# Thunder-Refix.net
KiCad netlist of a schematic drawn in Altium Designer
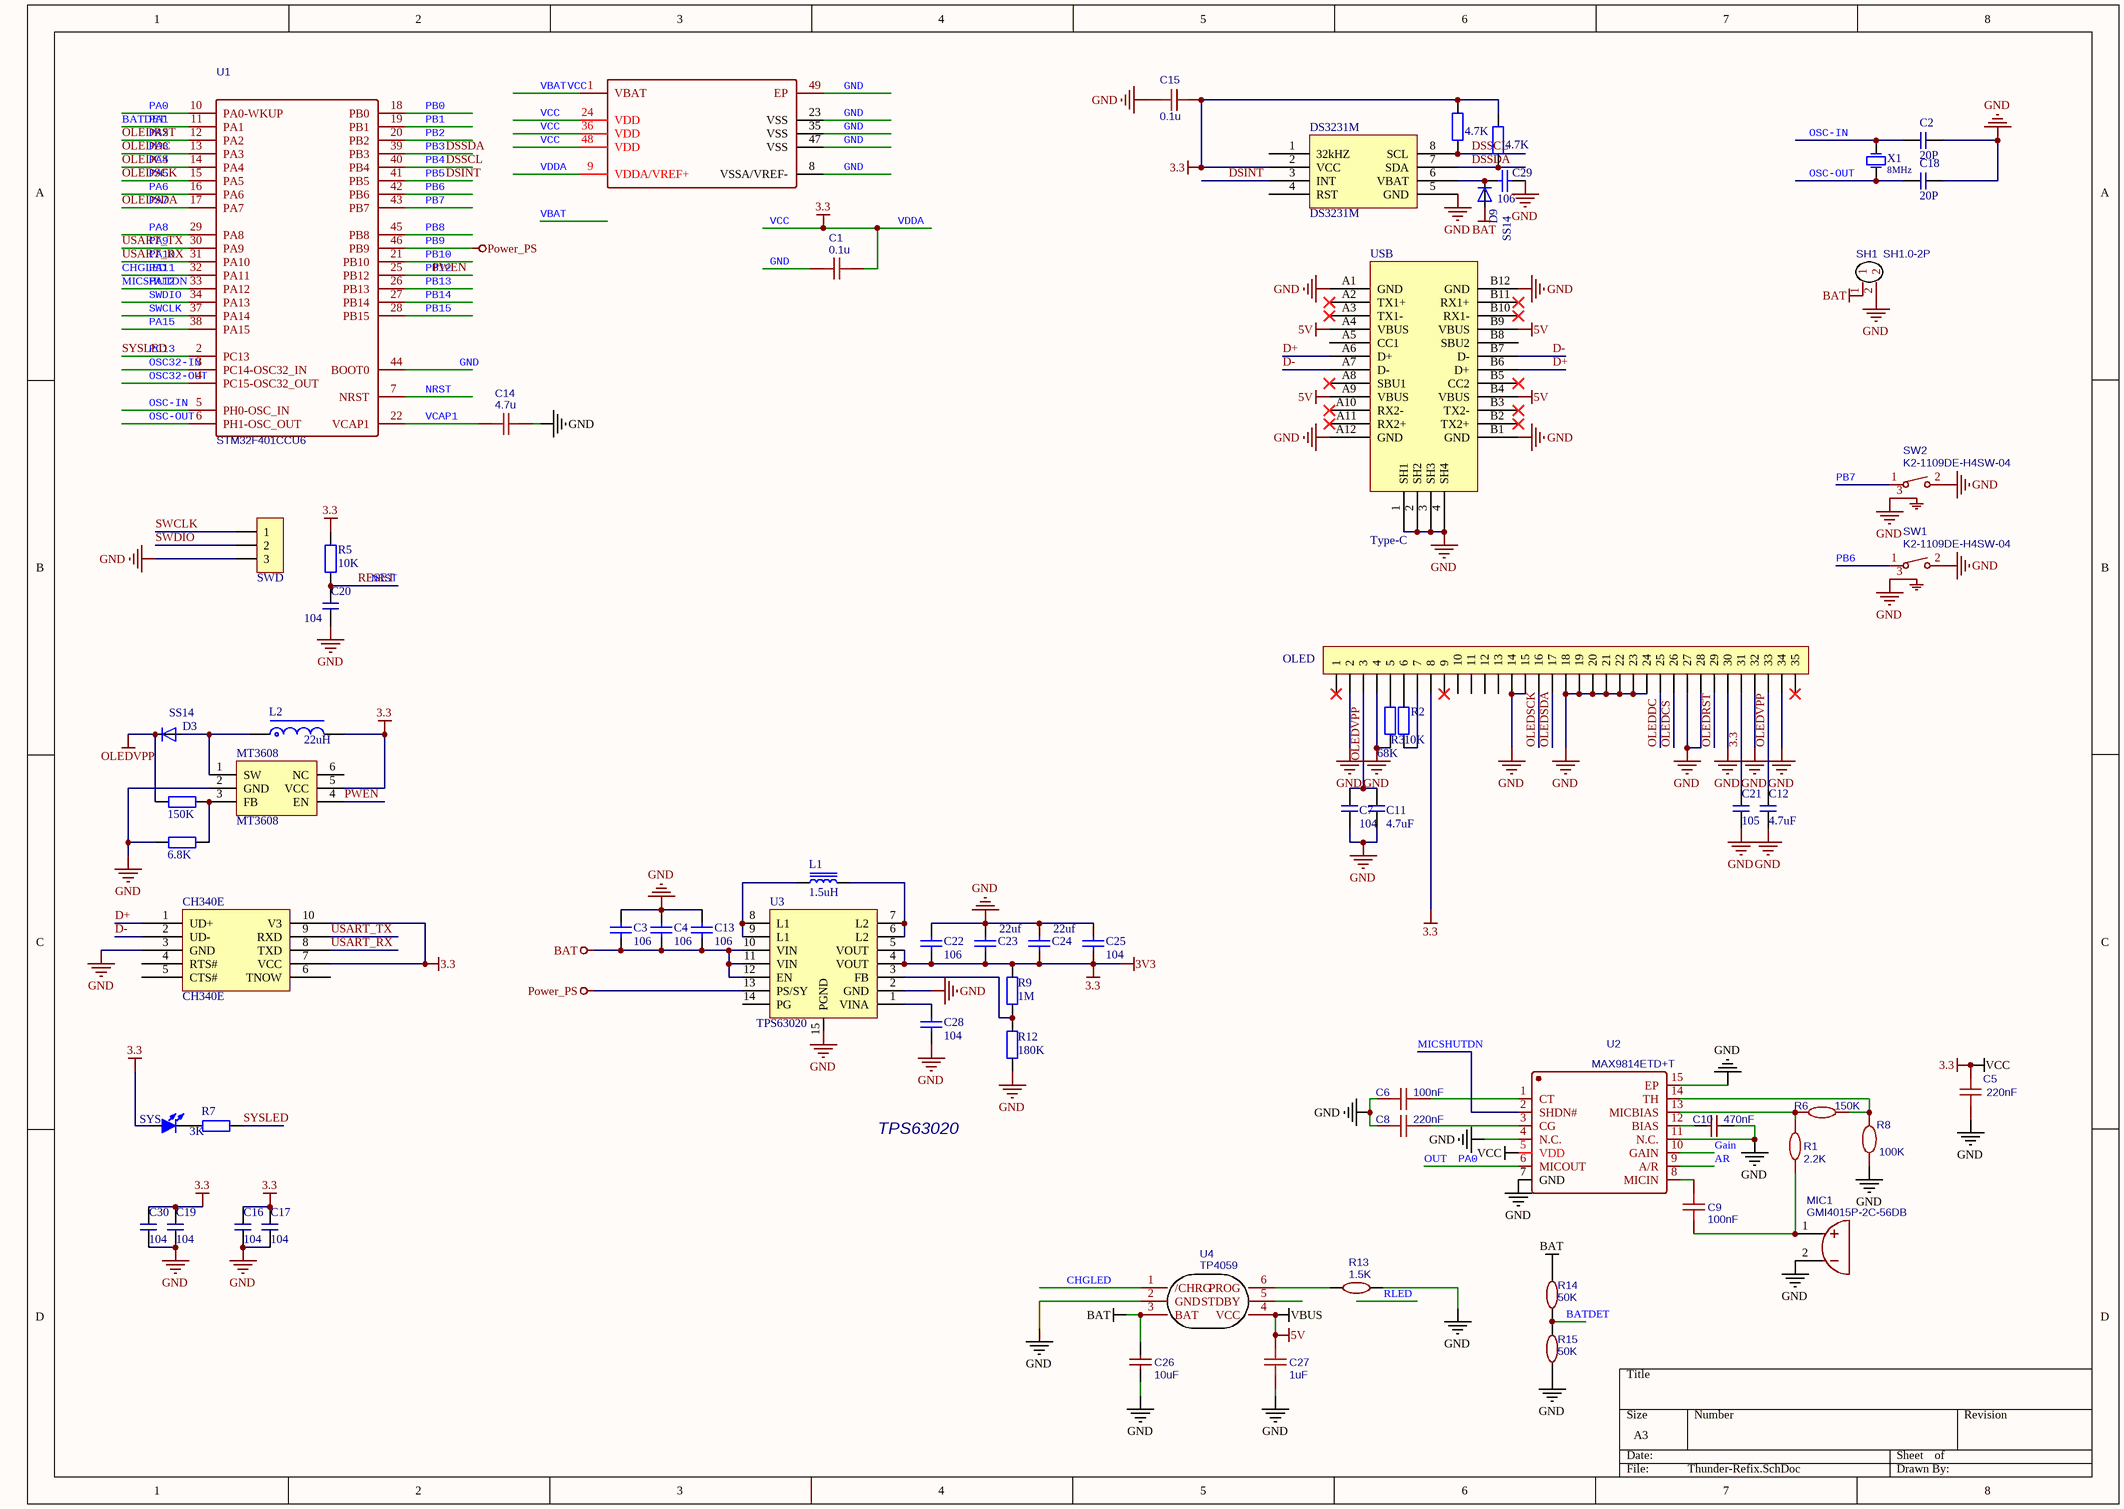
[diagram p0: Thunder-Refix.SchDoc]

(export (version "E")
  (design (tool "Eeschema 10.0.6"))
  (components
    (comp (ref "C1")
      (value "0.1u")
      (footprint "0603C")
      (fields (field (name "CONTRIBUTOR") "LCEDA_Lib"))
      (libsource (lib "altium-import") (part "root_2_0.1u_"))
    )
    (comp (ref "C2") (value "20P") (footprint "0603C") (libsource (lib "Schlib1") (part "电容")))
    (comp (ref "C3")
      (value "106")
      (footprint "我的PCB库:0603c")
      (fields (field (name "C") "106"))
      (libsource (lib "元件库") (part "cap"))
    )
    (comp (ref "C4")
      (value "106")
      (footprint "我的PCB库:0603c")
      (fields (field (name "C") "106"))
      (libsource (lib "元件库") (part "cap"))
    )
    (comp (ref "C5")
      (value "220nF")
      (footprint "0603c")
      (fields
        (field (name "BOM_SUPPLIER PART") "C354366")
        (field (name "BOM_MANUFACTURER PART") "GCJ21BR71H224KA01L")
        (field (name "CONTRIBUTOR") "LCSC")
      )
      (libsource (lib "altium-import") (part "root_1_220nF_"))
    )
    (comp (ref "C6")
      (value "100nF")
      (footprint "0603c")
      (fields
        (field (name "BOM_SUPPLIER PART") "C444732")
        (field (name "BOM_MANUFACTURER PART") "FS055C104K4Z2A")
        (field (name "CONTRIBUTOR") "LCSC")
      )
      (libsource (lib "altium-import") (part "root_1_100nF_"))
    )
    (comp (ref "C7") (value "104") (footprint "0603C") (libsource (lib "Schlib1") (part "电容")))
    (comp (ref "C8")
      (value "220nF")
      (footprint "0603c")
      (fields
        (field (name "BOM_SUPPLIER PART") "C354366")
        (field (name "BOM_MANUFACTURER PART") "GCJ21BR71H224KA01L")
        (field (name "CONTRIBUTOR") "LCSC")
      )
      (libsource (lib "altium-import") (part "root_0_220nF_"))
    )
    (comp (ref "C9")
      (value "100nF")
      (footprint "0603c")
      (fields
        (field (name "BOM_SUPPLIER PART") "C444732")
        (field (name "BOM_MANUFACTURER PART") "FS055C104K4Z2A")
        (field (name "CONTRIBUTOR") "LCSC")
      )
      (libsource (lib "altium-import") (part "root_0_100nF_"))
    )
    (comp (ref "C10")
      (value "470nF")
      (footprint "0603c")
      (fields
        (field (name "BOM_MANUFACTURER PART") "CL21B474KBFNNNE")
        (field (name "BOM_SUPPLIER PART") "C13967")
      )
      (libsource (lib "altium-import") (part "root_0_470nF_"))
    )
    (comp (ref "C11") (value "4.7uF") (footprint "0603C") (libsource (lib "Schlib1") (part "电容")))
    (comp (ref "C12") (value "4.7uF") (footprint "0603C") (libsource (lib "Schlib1") (part "电容")))
    (comp (ref "C13")
      (value "106")
      (footprint "0603c")
      (fields (field (name "C") "106"))
      (libsource (lib "元件库") (part "cap"))
    )
    (comp (ref "C14")
      (value "4.7u")
      (footprint "0603C")
      (fields (field (name "CONTRIBUTOR") "LCEDA_Lib"))
      (libsource (lib "altium-import") (part "root_0_4.7u_"))
    )
    (comp (ref "C15")
      (value "0.1u")
      (footprint "0603C")
      (fields (field (name "CONTRIBUTOR") "LCEDA_Lib"))
      (libsource (lib "altium-import") (part "root_2_0.1u_"))
    )
    (comp (ref "C16") (value "104") (footprint "0603C") (libsource (lib "Schlib1") (part "电容")))
    (comp (ref "C17") (value "104") (footprint "0603C") (libsource (lib "Schlib1") (part "电容")))
    (comp (ref "C18") (value "20P") (footprint "0603C") (libsource (lib "Schlib1") (part "电容")))
    (comp (ref "C19") (value "104") (footprint "0603C") (libsource (lib "Schlib1") (part "电容")))
    (comp (ref "C20") (value "104") (footprint "0603C") (libsource (lib "Schlib1") (part "电容")))
    (comp (ref "C21") (value "105") (footprint "0603C") (libsource (lib "Schlib1") (part "电容")))
    (comp (ref "C22")
      (value "106")
      (footprint "0603c")
      (fields (field (name "C") "106"))
      (libsource (lib "元件库") (part "cap"))
    )
    (comp (ref "C23")
      (value "22uf")
      (footprint "0603c")
      (fields (field (name "C") "22uf"))
      (libsource (lib "元件库") (part "cap"))
    )
    (comp (ref "C24")
      (value "22uf")
      (footprint "0603c")
      (fields (field (name "C") "22uf"))
      (libsource (lib "元件库") (part "cap"))
    )
    (comp (ref "C25")
      (value "104")
      (footprint "0603c")
      (fields (field (name "C") "104"))
      (libsource (lib "元件库") (part "cap"))
    )
    (comp (ref "C26")
      (value "10uF")
      (footprint "0603c")
      (fields
        (field (name "BOM_SUPPLIER PART") "C162317")
        (field (name "BOM_MANUFACTURER PART") "GRM21BB31C106KE15L")
        (field (name "CONTRIBUTOR") "LCSC")
      )
      (libsource (lib "altium-import") (part "root_1_10uF_"))
    )
    (comp (ref "C27")
      (value "1uF")
      (footprint "0603c")
      (fields
        (field (name "BOM_SUPPLIER PART") "C319195")
        (field (name "BOM_MANUFACTURER PART") "UMK212BJ105KG-T")
        (field (name "CONTRIBUTOR") "LCSC")
      )
      (libsource (lib "altium-import") (part "root_1_1uF_"))
    )
    (comp (ref "C28")
      (value "104")
      (footprint "0603c")
      (fields (field (name "C") "104"))
      (libsource (lib "元件库") (part "cap"))
    )
    (comp (ref "C29")
      (value "106")
      (footprint "0603c")
      (fields (field (name "C") "106"))
      (libsource (lib "元件库") (part "cap"))
    )
    (comp (ref "C30") (value "104") (footprint "0603C") (libsource (lib "Schlib1") (part "电容")))
    (comp (ref "CH340E") (value "CH340E") (footprint "MSOP10_L") (libsource (lib "CUBE_T1") (part "CH340E")))
    (comp (ref "D3")
      (value "SS14")
      (footprint "SOD323_1N4148WS")
      (description "Diode Switching 75V 0.3A 2-Pin SOD-323 T/R")
      (fields (field (name "MF") "ON Semiconductor") (field (name "MP") "1N4148WS"))
      (libsource (lib "1N4148WS") (part "1N4148WS"))
    )
    (comp (ref "D9")
      (value "SS14")
      (footprint "SOD323_1N4148WS")
      (description "Diode Switching 75V 0.3A 2-Pin SOD-323 T/R")
      (fields (field (name "MF") "ON Semiconductor") (field (name "MP") "1N4148WS"))
      (libsource (lib "1N4148WS") (part "1N4148WS"))
    )
    (comp (ref "DS3231M") (value "DS3231M") (footprint "SOP8") (libsource (lib "CUBE_T1") (part "DS3231M")))
    (comp (ref "L1")
      (value "1.5uH")
      (footprint "我的PCB库:IND-SMD_L3.0-W3.0_NR3010")
      (fields (field (name "_VALUE") "1.5uH"))
      (libsource (lib "元件库") (part "Inductor Iron 2"))
    )
    (comp (ref "L2")
      (value "22uH")
      (footprint "IND-SMD_L3.0-W3.0_NR3010")
      (description "功率屏蔽电感")
      (fields (field (name "版权归属") "源创客"))
      (libsource (lib "3.1   - 电阻-电容-电感") (part "L-CDRH"))
    )
    (comp (ref "MIC1")
      (value "GMI4015P-2C-56DB")
      (footprint "MIC-TH_BD4.0-P2.00-D0.4-L-FD")
      (fields
        (field (name "BOM_SUPPLIER PART") "C233299")
        (field (name "BOM_MANUFACTURER PART") "GMI4015P-2C-56db")
        (field (name "CONTRIBUTOR") "LCSC")
      )
      (libsource (lib "altium-import") (part "root_0_GMI4015P-2C-56DB_"))
    )
    (comp (ref "MT3608")
      (value "MT3608")
      (footprint "SOT23-6N")
      (description "可调升压芯片")
      (fields (field (name "版权归属") "源创客"))
      (libsource (lib "1.3   - 电源类芯片") (part "SX1308"))
    )
    (comp (ref "OLED")
      (value "FPC1.0-35P")
      (footprint "1.69 OLED")
      (description "FPC连接器")
      (fields (field (name "版权归属") "源创客"))
      (libsource (lib "4.14 - FPC连接器") (part "FPC-35P"))
    )
    (comp (ref "R1")
      (value "2.2K")
      (footprint "0603r")
      (fields
        (field (name "BOM_SUPPLIER PART") "C325769")
        (field (name "BOM_MANUFACTURER PART") "RMC08052.2K1%N")
        (field (name "CONTRIBUTOR") "LCSC")
      )
      (libsource (lib "altium-import") (part "root_1_2.2K_"))
    )
    (comp (ref "R2")
      (value "10K")
      (footprint "0603R")
      (description "贴片电阻")
      (fields (field (name "版权归属") "源创客"))
      (libsource (lib "3.1   - 电阻-电容-电感") (part "R"))
    )
    (comp (ref "R3")
      (value "68K")
      (footprint "0603R")
      (description "贴片电阻")
      (fields (field (name "版权归属") "源创客"))
      (libsource (lib "3.1   - 电阻-电容-电感") (part "R"))
    )
    (comp (ref "R5")
      (value "10K")
      (footprint "0603R")
      (description "贴片电阻")
      (fields (field (name "版权归属") "源创客"))
      (libsource (lib "3.1   - 电阻-电容-电感") (part "R"))
    )
    (comp (ref "R6")
      (value "150K")
      (footprint "0603r")
      (fields
        (field (name "BOM_SUPPLIER PART") "C325765")
        (field (name "BOM_MANUFACTURER PART") "RMC0805150K1%N")
        (field (name "CONTRIBUTOR") "LCSC")
      )
      (libsource (lib "altium-import") (part "root_0_150K_"))
    )
    (comp (ref "R7")
      (value "3K")
      (footprint "0603R")
      (description "贴片电阻")
      (fields (field (name "版权归属") "源创客"))
      (libsource (lib "3.1   - 电阻-电容-电感") (part "R"))
    )
    (comp (ref "R8")
      (value "100K")
      (footprint "0603r")
      (fields
        (field (name "BOM_SUPPLIER PART") "C346756")
        (field (name "BOM_MANUFACTURER PART") "RTAN0805BKE100K")
        (field (name "CONTRIBUTOR") "LCSC")
      )
      (libsource (lib "altium-import") (part "root_1_100K_"))
    )
    (comp (ref "R9")
      (value "1M")
      (footprint "0603r")
      (fields (field (name "R") "1M"))
      (libsource (lib "元件库") (part "Res"))
    )
    (comp (ref "R10")
      (value "4.7K")
      (footprint "0603R")
      (description "贴片电阻")
      (fields (field (name "版权归属") "源创客"))
      (libsource (lib "3.1   - 电阻-电容-电感") (part "R"))
    )
    (comp (ref "R11")
      (value "4.7K")
      (footprint "0603R")
      (description "贴片电阻")
      (fields (field (name "版权归属") "源创客"))
      (libsource (lib "3.1   - 电阻-电容-电感") (part "R"))
    )
    (comp (ref "R12")
      (value "180K")
      (footprint "0603r")
      (fields (field (name "R") "180K"))
      (libsource (lib "元件库") (part "Res"))
    )
    (comp (ref "R13")
      (value "1.5K")
      (footprint "0603r")
      (fields
        (field (name "BOM_MANUFACTURER PART") "RC0603FR-071K5L")
        (field (name "BOM_SUPPLIER PART") "C114668")
      )
      (libsource (lib "altium-import") (part "root_0_1.5K_"))
    )
    (comp (ref "R14")
      (value "50K")
      (footprint "0603r")
      (fields
        (field (name "BOM_MANUFACTURER PART") "RC0603FR-071K5L")
        (field (name "BOM_SUPPLIER PART") "C114668")
      )
      (libsource (lib "altium-import") (part "root_1_1.5K_"))
    )
    (comp (ref "R15")
      (value "50K")
      (footprint "0603r")
      (fields
        (field (name "BOM_MANUFACTURER PART") "RC0603FR-071K5L")
        (field (name "BOM_SUPPLIER PART") "C114668")
      )
      (libsource (lib "altium-import") (part "root_1_1.5K_"))
    )
    (comp (ref "RB")
      (value "150K")
      (footprint "0603R")
      (description "贴片电阻")
      (fields (field (name "版权归属") "源创客"))
      (libsource (lib "3.1   - 电阻-电容-电感") (part "R"))
    )
    (comp (ref "RS")
      (value "6.8K")
      (footprint "0603R")
      (description "贴片电阻")
      (fields (field (name "版权归属") "源创客"))
      (libsource (lib "3.1   - 电阻-电容-电感") (part "R"))
    )
    (comp (ref "SH1")
      (value "SH1.0-2P")
      (footprint "SH1.0-2P")
      (fields (field (name "CONTRIBUTOR") "perry2867"))
      (libsource (lib "altium-import") (part "root_1_SH1.0-2P_"))
    )
    (comp (ref "SW1")
      (value "K2-1109DE-H4SW-04")
      (footprint "KEY-TH_K2-1109DE-CXXW-XX")
      (fields (field (name "BOM_SUPPLIER PART") "C961730") (field (name "CONTRIBUTOR") "LCSC"))
      (libsource (lib "altium-import") (part "root_0_K2-1109DE-H4SW-04_"))
    )
    (comp (ref "SW2")
      (value "K2-1109DE-H4SW-04")
      (footprint "KEY-TH_K2-1109DE-CXXW-XX")
      (fields (field (name "BOM_SUPPLIER PART") "C961730") (field (name "CONTRIBUTOR") "LCSC"))
      (libsource (lib "altium-import") (part "root_0_K2-1109DE-H4SW-04_"))
    )
    (comp (ref "SWD")
      (value "HDR-1X3")
      (footprint "ZH1.5-LI-3P")
      (description "3P接插件")
      (fields (field (name "版权归属") "源创客"))
      (libsource (lib "4.3   - 接插件-脚距1.5") (part "Header 3"))
    )
    (comp (ref "SYS")
      (value "粉色")
      (footprint "0603LED")
      (description "方形LED")
      (fields (field (name "版权归属") "源创客"))
      (libsource (lib "9.1   - LED") (part "LED-F234"))
    )
    (comp (ref "U1")
      (value "STM32F401CCU6")
      (footprint "QFN48 7X7_N")
      (fields (field (name "BOM_SUPPLIER PART") "C79861") (field (name "SUBPART_NO") "1"))
      (libsource (lib "Galaxy") (part "STM32F401CCU6"))
    )
    (comp (ref "U2")
      (value "MAX9814ETD+T")
      (footprint "TDFN-14_L3.0-W3.0-P0.40-BL-EP")
      (fields (field (name "BOM_SUPPLIER PART") "C41714"))
      (libsource (lib "altium-import") (part "root_0_MAX9814ETD+T_"))
    )
    (comp (ref "U3")
      (value "TPS63020")
      (footprint "我的PCB库:TPS63020")
      (libsource (lib "我的元件库") (part "TPS63020"))
    )
    (comp (ref "U4")
      (value "TP4059")
      (footprint "SOT23-6N")
      (fields (field (name "BOM_SUPPLIER PART") "C80364"))
      (libsource (lib "altium-import") (part "root_0_TP4059_"))
    )
    (comp (ref "USB") (value "Type-C") (footprint "Type-C") (libsource (lib "元件") (part "Type-C")))
    (comp (ref "X1")
      (value "8MHz")
      (footprint "OSC 5032-2P")
      (description "XTAL,8MHz,±20PPM,12.6*4.5")
      (fields (field (name "Comment") "1.6.1.01.005.001"))
      (libsource (lib "Mark_7") (part "1.6.1.01.005.001"))
    )
  )
  (nets
    (net (code "1") (name "/AR") (class "Default")
      (node (ref "U2") (pin "9") (pinfunction "A/R_9") (pintype "passive"))
    )
    (net (code "2") (name "/BATDET") (class "Default")
      (node (ref "R14") (pin "1") (pinfunction "1_1") (pintype "passive"))
      (node (ref "R15") (pin "2") (pinfunction "2_2") (pintype "passive"))
      (node (ref "U1") (pin "11") (pinfunction "PA1_11") (pintype "passive"))
    )
    (net (code "3") (name "/CHGLED") (class "Default")
      (node (ref "U1") (pin "32") (pinfunction "PA11_32") (pintype "passive"))
      (node (ref "U4") (pin "1") (pinfunction "/CHRG_1") (pintype "passive"))
    )
    (net (code "4") (name "/D+") (class "Default")
      (node (ref "CH340E") (pin "1") (pinfunction "UD+_1") (pintype "passive"))
      (node (ref "USB") (pin "A6") (pinfunction "D+_A6") (pintype "passive"))
      (node (ref "USB") (pin "B6") (pinfunction "D+_B6") (pintype "passive"))
    )
    (net (code "5") (name "/D-") (class "Default")
      (node (ref "CH340E") (pin "2") (pinfunction "UD-_2") (pintype "passive"))
      (node (ref "USB") (pin "A7") (pinfunction "D-_A7") (pintype "passive"))
      (node (ref "USB") (pin "B7") (pinfunction "D-_B7") (pintype "passive"))
    )
    (net (code "6") (name "/DSINT") (class "Default")
      (node (ref "DS3231M") (pin "3") (pinfunction "INT_3") (pintype "passive"))
      (node (ref "U1") (pin "41") (pinfunction "PB5_41") (pintype "passive"))
    )
    (net (code "7") (name "/DSSCL") (class "Default")
      (node (ref "DS3231M") (pin "8") (pinfunction "SCL_8") (pintype "passive"))
      (node (ref "R10") (pin "2") (pinfunction "2_2") (pintype "passive"))
      (node (ref "U1") (pin "40") (pinfunction "PB4_40") (pintype "passive"))
    )
    (net (code "8") (name "/DSSDA") (class "Default")
      (node (ref "DS3231M") (pin "7") (pinfunction "SDA_7") (pintype "passive"))
      (node (ref "R11") (pin "2") (pinfunction "2_2") (pintype "passive"))
      (node (ref "U1") (pin "39") (pinfunction "PB3_39") (pintype "passive"))
    )
    (net (code "9") (name "/Gain") (class "Default")
      (node (ref "U2") (pin "10") (pinfunction "GAIN_10") (pintype "passive"))
    )
    (net (code "10") (name "/MICSHUTDN") (class "Default")
      (node (ref "U1") (pin "33") (pinfunction "PA12_33") (pintype "passive"))
      (node (ref "U2") (pin "2") (pinfunction "SHDN#_2") (pintype "passive"))
    )
    (net (code "11") (name "/NRST") (class "Default")
      (node (ref "C20") (pin "1") (pinfunction "1_1") (pintype "passive"))
      (node (ref "R5") (pin "2") (pinfunction "2_2") (pintype "passive"))
      (node (ref "U1") (pin "7") (pinfunction "NRST_7") (pintype "passive"))
    )
    (net (code "12") (name "/OLEDCS") (class "Default")
      (node (ref "OLED") (pin "26") (pinfunction "26_26") (pintype "passive"))
      (node (ref "U1") (pin "14") (pinfunction "PA4_14") (pintype "passive"))
    )
    (net (code "13") (name "/OLEDDC") (class "Default")
      (node (ref "OLED") (pin "25") (pinfunction "25_25") (pintype "passive"))
      (node (ref "U1") (pin "13") (pinfunction "PA3_13") (pintype "passive"))
    )
    (net (code "14") (name "/OLEDRST") (class "Default")
      (node (ref "OLED") (pin "29") (pinfunction "29_29") (pintype "passive"))
      (node (ref "U1") (pin "12") (pinfunction "PA2_12") (pintype "passive"))
    )
    (net (code "15") (name "/OLEDSCK") (class "Default")
      (node (ref "OLED") (pin "16") (pinfunction "16_16") (pintype "passive"))
      (node (ref "U1") (pin "15") (pinfunction "PA5_15") (pintype "passive"))
    )
    (net (code "16") (name "/OLEDSDA") (class "Default")
      (node (ref "OLED") (pin "17") (pinfunction "17_17") (pintype "passive"))
      (node (ref "U1") (pin "17") (pinfunction "PA7_17") (pintype "passive"))
    )
    (net (code "17") (name "/OSC-IN") (class "Default")
      (node (ref "C2") (pin "2") (pinfunction "2_2") (pintype "passive"))
      (node (ref "U1") (pin "5") (pinfunction "PH0-OSC_IN_5") (pintype "passive"))
      (node (ref "X1") (pin "1") (pinfunction "OSC1_1") (pintype "passive"))
    )
    (net (code "18") (name "/OSC-OUT") (class "Default")
      (node (ref "C18") (pin "2") (pinfunction "2_2") (pintype "passive"))
      (node (ref "U1") (pin "6") (pinfunction "PH1-OSC_OUT_6") (pintype "passive"))
      (node (ref "X1") (pin "2") (pinfunction "OSC2_2") (pintype "passive"))
    )
    (net (code "19") (name "/OSC32-IN") (class "Default")
      (node (ref "U1") (pin "3") (pinfunction "PC14-OSC32_IN_3") (pintype "passive"))
    )
    (net (code "20") (name "/OSC32-OUT") (class "Default")
      (node (ref "U1") (pin "4") (pinfunction "PC15-OSC32_OUT_4") (pintype "passive"))
    )
    (net (code "21") (name "/OUT") (class "Default")
      (node (ref "U1") (pin "10") (pinfunction "PA0-WKUP_10") (pintype "passive"))
      (node (ref "U2") (pin "6") (pinfunction "MICOUT_6") (pintype "passive"))
    )
    (net (code "22") (name "/PA6") (class "Default")
      (node (ref "U1") (pin "16") (pinfunction "PA6_16") (pintype "passive"))
    )
    (net (code "23") (name "/PA8") (class "Default")
      (node (ref "U1") (pin "29") (pinfunction "PA8_29") (pintype "passive"))
    )
    (net (code "24") (name "/PA9") (class "Default")
      (node (ref "CH340E") (pin "9") (pinfunction "RXD_9") (pintype "passive"))
      (node (ref "U1") (pin "30") (pinfunction "PA9_30") (pintype "passive"))
    )
    (net (code "25") (name "/PA10") (class "Default")
      (node (ref "CH340E") (pin "8") (pinfunction "TXD_8") (pintype "passive"))
      (node (ref "U1") (pin "31") (pinfunction "PA10_31") (pintype "passive"))
    )
    (net (code "26") (name "/PA15") (class "Default")
      (node (ref "U1") (pin "38") (pinfunction "PA15_38") (pintype "passive"))
    )
    (net (code "27") (name "/PB0") (class "Default")
      (node (ref "U1") (pin "18") (pinfunction "PB0_18") (pintype "passive"))
    )
    (net (code "28") (name "/PB1") (class "Default")
      (node (ref "U1") (pin "19") (pinfunction "PB1_19") (pintype "passive"))
    )
    (net (code "29") (name "/PB2") (class "Default")
      (node (ref "U1") (pin "20") (pinfunction "PB2_20") (pintype "passive"))
    )
    (net (code "30") (name "/PB6") (class "Default")
      (node (ref "SW1") (pin "1") (pinfunction "1_1") (pintype "passive"))
      (node (ref "U1") (pin "42") (pinfunction "PB6_42") (pintype "passive"))
    )
    (net (code "31") (name "/PB7") (class "Default")
      (node (ref "SW2") (pin "1") (pinfunction "1_1") (pintype "passive"))
      (node (ref "U1") (pin "43") (pinfunction "PB7_43") (pintype "passive"))
    )
    (net (code "32") (name "/PB8") (class "Default")
      (node (ref "U1") (pin "45") (pinfunction "PB8_45") (pintype "passive"))
    )
    (net (code "33") (name "/PB10") (class "Default")
      (node (ref "U1") (pin "21") (pinfunction "PB10_21") (pintype "passive"))
    )
    (net (code "34") (name "/PB12") (class "Default")
      (node (ref "MT3608") (pin "4") (pinfunction "EN_4") (pintype "passive"))
      (node (ref "U1") (pin "25") (pinfunction "PB12_25") (pintype "passive"))
    )
    (net (code "35") (name "/PB13") (class "Default")
      (node (ref "U1") (pin "26") (pinfunction "PB13_26") (pintype "passive"))
    )
    (net (code "36") (name "/PB14") (class "Default")
      (node (ref "U1") (pin "27") (pinfunction "PB14_27") (pintype "passive"))
    )
    (net (code "37") (name "/PB15") (class "Default")
      (node (ref "U1") (pin "28") (pinfunction "PB15_28") (pintype "passive"))
    )
    (net (code "38") (name "/PC13") (class "Default")
      (node (ref "R7") (pin "1") (pinfunction "1_1") (pintype "passive"))
      (node (ref "U1") (pin "2") (pinfunction "PC13_2") (pintype "passive"))
    )
    (net (code "40") (name "/SWCLK") (class "Default")
      (node (ref "SWD") (pin "1") (pinfunction "1_1") (pintype "passive"))
      (node (ref "U1") (pin "37") (pinfunction "PA14_37") (pintype "passive"))
    )
    (net (code "41") (name "/SWDIO") (class "Default")
      (node (ref "SWD") (pin "2") (pinfunction "2_2") (pintype "passive"))
      (node (ref "U1") (pin "34") (pinfunction "PA13_34") (pintype "passive"))
    )
    (net (code "42") (name "/VCAP1") (class "Default")
      (node (ref "C14") (pin "1") (pinfunction "1_1") (pintype "passive"))
      (node (ref "U1") (pin "22") (pinfunction "VCAP1_22") (pintype "passive"))
    )
    (net (code "43") (name "3.3") (class "Default")
      (node (ref "C1") (pin "1") (pinfunction "1_1") (pintype "passive"))
      (node (ref "C15") (pin "1") (pinfunction "1_1") (pintype "passive"))
      (node (ref "C16") (pin "1") (pinfunction "1_1") (pintype "passive"))
      (node (ref "C17") (pin "1") (pinfunction "1_1") (pintype "passive"))
      (node (ref "C19") (pin "1") (pinfunction "1_1") (pintype "passive"))
      (node (ref "C21") (pin "1") (pinfunction "1_1") (pintype "passive"))
      (node (ref "C22") (pin "1") (pinfunction "1_1") (pintype "passive"))
      (node (ref "C23") (pin "1") (pinfunction "1_1") (pintype "passive"))
      (node (ref "C24") (pin "1") (pinfunction "1_1") (pintype "passive"))
      (node (ref "C25") (pin "1") (pinfunction "1_1") (pintype "passive"))
      (node (ref "C30") (pin "1") (pinfunction "1_1") (pintype "passive"))
      (node (ref "C5") (pin "2") (pinfunction "2_2") (pintype "passive"))
      (node (ref "CH340E") (pin "10") (pinfunction "V3_10") (pintype "passive"))
      (node (ref "CH340E") (pin "7") (pinfunction "VCC_7") (pintype "passive"))
      (node (ref "DS3231M") (pin "2") (pinfunction "VCC_2") (pintype "passive"))
      (node (ref "L2") (pin "2") (pinfunction "2_2") (pintype "passive"))
      (node (ref "MT3608") (pin "5") (pinfunction "VCC_5") (pintype "passive"))
      (node (ref "OLED") (pin "31") (pinfunction "31_31") (pintype "passive"))
      (node (ref "OLED") (pin "8") (pinfunction "8_8") (pintype "passive"))
      (node (ref "R10") (pin "1") (pinfunction "1_1") (pintype "passive"))
      (node (ref "R11") (pin "1") (pinfunction "1_1") (pintype "passive"))
      (node (ref "R5") (pin "1") (pinfunction "1_1") (pintype "passive"))
      (node (ref "R9") (pin "1") (pinfunction "1_1") (pintype "passive"))
      (node (ref "SYS") (pin "1") (pinfunction "A_1") (pintype "passive"))
      (node (ref "U1") (pin "1") (pinfunction "VBAT_1") (pintype "passive"))
      (node (ref "U1") (pin "24") (pinfunction "VDD_24") (pintype "passive"))
      (node (ref "U1") (pin "36") (pinfunction "VDD_36") (pintype "passive"))
      (node (ref "U1") (pin "48") (pinfunction "VDD_48") (pintype "passive"))
      (node (ref "U1") (pin "9") (pinfunction "VDDA/VREF+_9") (pintype "passive"))
      (node (ref "U2") (pin "5") (pinfunction "VDD_5") (pintype "passive"))
      (node (ref "U3") (pin "4") (pinfunction "VOUT_4") (pintype "passive"))
      (node (ref "U3") (pin "5") (pinfunction "VOUT_5") (pintype "passive"))
    )
    (net (code "44") (name "5V") (class "Default")
      (node (ref "C27") (pin "1") (pinfunction "1_1") (pintype "passive"))
      (node (ref "U4") (pin "4") (pinfunction "VCC_4") (pintype "passive"))
      (node (ref "USB") (pin "A4") (pinfunction "VBUS_A4") (pintype "passive"))
      (node (ref "USB") (pin "A9") (pinfunction "VBUS_A9") (pintype "passive"))
      (node (ref "USB") (pin "B4") (pinfunction "VBUS_B4") (pintype "passive"))
      (node (ref "USB") (pin "B9") (pinfunction "VBUS_B9") (pintype "passive"))
    )
    (net (code "45") (name "BAT") (class "Default")
      (node (ref "C13") (pin "1") (pinfunction "1_1") (pintype "passive"))
      (node (ref "C26") (pin "2") (pinfunction "2_2") (pintype "passive"))
      (node (ref "C3") (pin "1") (pinfunction "1_1") (pintype "passive"))
      (node (ref "C4") (pin "1") (pinfunction "1_1") (pintype "passive"))
      (node (ref "D9") (pin "A") (pinfunction "A_A") (pintype "passive"))
      (node (ref "R14") (pin "2") (pinfunction "2_2") (pintype "passive"))
      (node (ref "SH1") (pin "1") (pinfunction "1_1") (pintype "passive"))
      (node (ref "U3") (pin "10") (pinfunction "VIN_10") (pintype "passive"))
      (node (ref "U3") (pin "11") (pinfunction "VIN_11") (pintype "passive"))
      (node (ref "U3") (pin "12") (pinfunction "EN_12") (pintype "passive"))
      (node (ref "U4") (pin "3") (pinfunction "BAT_3") (pintype "passive"))
    )
    (net (code "46") (name "GND") (class "Default")
      (node (ref "C1") (pin "2") (pinfunction "2_2") (pintype "passive"))
      (node (ref "C10") (pin "2") (pinfunction "2_2") (pintype "passive"))
      (node (ref "C11") (pin "2") (pinfunction "2_2") (pintype "passive"))
      (node (ref "C12") (pin "2") (pinfunction "2_2") (pintype "passive"))
      (node (ref "C13") (pin "2") (pinfunction "2_2") (pintype "passive"))
      (node (ref "C14") (pin "2") (pinfunction "2_2") (pintype "passive"))
      (node (ref "C15") (pin "2") (pinfunction "2_2") (pintype "passive"))
      (node (ref "C16") (pin "2") (pinfunction "2_2") (pintype "passive"))
      (node (ref "C17") (pin "2") (pinfunction "2_2") (pintype "passive"))
      (node (ref "C18") (pin "1") (pinfunction "1_1") (pintype "passive"))
      (node (ref "C19") (pin "2") (pinfunction "2_2") (pintype "passive"))
      (node (ref "C2") (pin "1") (pinfunction "1_1") (pintype "passive"))
      (node (ref "C20") (pin "2") (pinfunction "2_2") (pintype "passive"))
      (node (ref "C21") (pin "2") (pinfunction "2_2") (pintype "passive"))
      (node (ref "C22") (pin "2") (pinfunction "2_2") (pintype "passive"))
      (node (ref "C23") (pin "2") (pinfunction "2_2") (pintype "passive"))
      (node (ref "C24") (pin "2") (pinfunction "2_2") (pintype "passive"))
      (node (ref "C25") (pin "2") (pinfunction "2_2") (pintype "passive"))
      (node (ref "C26") (pin "1") (pinfunction "1_1") (pintype "passive"))
      (node (ref "C27") (pin "2") (pinfunction "2_2") (pintype "passive"))
      (node (ref "C28") (pin "1") (pinfunction "1_1") (pintype "passive"))
      (node (ref "C29") (pin "1") (pinfunction "1_1") (pintype "passive"))
      (node (ref "C3") (pin "2") (pinfunction "2_2") (pintype "passive"))
      (node (ref "C30") (pin "2") (pinfunction "2_2") (pintype "passive"))
      (node (ref "C4") (pin "2") (pinfunction "2_2") (pintype "passive"))
      (node (ref "C5") (pin "1") (pinfunction "1_1") (pintype "passive"))
      (node (ref "C6") (pin "1") (pinfunction "1_1") (pintype "passive"))
      (node (ref "C7") (pin "2") (pinfunction "2_2") (pintype "passive"))
      (node (ref "C8") (pin "1") (pinfunction "1_1") (pintype "passive"))
      (node (ref "CH340E") (pin "3") (pinfunction "GND_3") (pintype "passive"))
      (node (ref "DS3231M") (pin "5") (pinfunction "GND_5") (pintype "passive"))
      (node (ref "MIC1") (pin "2") (pinfunction "2_2") (pintype "passive"))
      (node (ref "MT3608") (pin "2") (pinfunction "GND_2") (pintype "passive"))
      (node (ref "OLED") (pin "14") (pinfunction "14_14") (pintype "passive"))
      (node (ref "OLED") (pin "15") (pinfunction "15_15") (pintype "passive"))
      (node (ref "OLED") (pin "18") (pinfunction "18_18") (pintype "passive"))
      (node (ref "OLED") (pin "19") (pinfunction "19_19") (pintype "passive"))
      (node (ref "OLED") (pin "2") (pinfunction "2_2") (pintype "passive"))
      (node (ref "OLED") (pin "20") (pinfunction "20_20") (pintype "passive"))
      (node (ref "OLED") (pin "21") (pinfunction "21_21") (pintype "passive"))
      (node (ref "OLED") (pin "22") (pinfunction "22_22") (pintype "passive"))
      (node (ref "OLED") (pin "23") (pinfunction "23_23") (pintype "passive"))
      (node (ref "OLED") (pin "24") (pinfunction "24_24") (pintype "passive"))
      (node (ref "OLED") (pin "27") (pinfunction "27_27") (pintype "passive"))
      (node (ref "OLED") (pin "28") (pinfunction "28_28") (pintype "passive"))
      (node (ref "OLED") (pin "30") (pinfunction "30_30") (pintype "passive"))
      (node (ref "OLED") (pin "32") (pinfunction "32_32") (pintype "passive"))
      (node (ref "OLED") (pin "34") (pinfunction "34_34") (pintype "passive"))
      (node (ref "OLED") (pin "4") (pinfunction "4_4") (pintype "passive"))
      (node (ref "R12") (pin "2") (pinfunction "2_2") (pintype "passive"))
      (node (ref "R13") (pin "2") (pinfunction "2_2") (pintype "passive"))
      (node (ref "R15") (pin "1") (pinfunction "1_1") (pintype "passive"))
      (node (ref "R3") (pin "1") (pinfunction "1_1") (pintype "passive"))
      (node (ref "R8") (pin "1") (pinfunction "1_1") (pintype "passive"))
      (node (ref "RS") (pin "1") (pinfunction "1_1") (pintype "passive"))
      (node (ref "SH1") (pin "2") (pinfunction "2_2") (pintype "passive"))
      (node (ref "SW1") (pin "2") (pinfunction "2_2") (pintype "passive"))
      (node (ref "SW1") (pin "3") (pinfunction "GND_3") (pintype "passive"))
      (node (ref "SW2") (pin "2") (pinfunction "2_2") (pintype "passive"))
      (node (ref "SW2") (pin "3") (pinfunction "GND_3") (pintype "passive"))
      (node (ref "SWD") (pin "3") (pinfunction "3_3") (pintype "passive"))
      (node (ref "U1") (pin "23") (pinfunction "VSS_23") (pintype "passive"))
      (node (ref "U1") (pin "35") (pinfunction "VSS_35") (pintype "passive"))
      (node (ref "U1") (pin "44") (pinfunction "BOOT0_44") (pintype "passive"))
      (node (ref "U1") (pin "47") (pinfunction "VSS_47") (pintype "passive"))
      (node (ref "U1") (pin "49") (pinfunction "EP_49") (pintype "passive"))
      (node (ref "U1") (pin "8") (pinfunction "VSSA/VREF-_8") (pintype "passive"))
      (node (ref "U2") (pin "11") (pinfunction "N.C._11") (pintype "passive"))
      (node (ref "U2") (pin "15") (pinfunction "EP_15") (pintype "passive"))
      (node (ref "U2") (pin "4") (pinfunction "N.C._4") (pintype "passive"))
      (node (ref "U2") (pin "7") (pinfunction "GND_7") (pintype "passive"))
      (node (ref "U3") (pin "15") (pinfunction "PGND_15") (pintype "passive"))
      (node (ref "U3") (pin "2") (pinfunction "GND_2") (pintype "passive"))
      (node (ref "U4") (pin "2") (pinfunction "GND_2") (pintype "passive"))
      (node (ref "USB") (pin "1") (pinfunction "SH1_1") (pintype "passive"))
      (node (ref "USB") (pin "2") (pinfunction "SH2_2") (pintype "passive"))
      (node (ref "USB") (pin "3") (pinfunction "SH3_3") (pintype "passive"))
      (node (ref "USB") (pin "4") (pinfunction "SH4_4") (pintype "passive"))
      (node (ref "USB") (pin "A1") (pinfunction "GND_A1") (pintype "passive"))
      (node (ref "USB") (pin "A12") (pinfunction "GND_A12") (pintype "passive"))
      (node (ref "USB") (pin "B1") (pinfunction "GND_B1") (pintype "passive"))
      (node (ref "USB") (pin "B12") (pinfunction "GND_B12") (pintype "passive"))
    )
    (net (code "47") (name "Net-(C9-Pad2)") (class "Default")
      (node (ref "C9") (pin "2") (pinfunction "2_2") (pintype "passive"))
      (node (ref "MIC1") (pin "1") (pinfunction "1_1") (pintype "passive"))
      (node (ref "R1") (pin "1") (pinfunction "1_1") (pintype "passive"))
    )
    (net (code "48") (name "Net-(DS3231M-VBAT)") (class "Default")
      (node (ref "C29") (pin "2") (pinfunction "2_2") (pintype "passive"))
      (node (ref "D9") (pin "C") (pinfunction "C_C") (pintype "passive"))
      (node (ref "DS3231M") (pin "6") (pinfunction "VBAT_6") (pintype "passive"))
    )
    (net (code "49") (name "Net-(L1-Pad1)") (class "Default")
      (node (ref "L1") (pin "1") (pinfunction "1_1") (pintype "passive"))
      (node (ref "U3") (pin "8") (pinfunction "L1_8") (pintype "passive"))
      (node (ref "U3") (pin "9") (pinfunction "L1_9") (pintype "passive"))
    )
    (net (code "50") (name "Net-(L1-Pad2)") (class "Default")
      (node (ref "L1") (pin "2") (pinfunction "2_2") (pintype "passive"))
      (node (ref "U3") (pin "6") (pinfunction "L2_6") (pintype "passive"))
      (node (ref "U3") (pin "7") (pinfunction "L2_7") (pintype "passive"))
    )
    (net (code "51") (name "Net-(MT3608-FB)") (class "Default")
      (node (ref "MT3608") (pin "3") (pinfunction "FB_3") (pintype "passive"))
      (node (ref "RB") (pin "2") (pinfunction "2_2") (pintype "passive"))
      (node (ref "RS") (pin "2") (pinfunction "2_2") (pintype "passive"))
    )
    (net (code "52") (name "Net-(MT3608-SW)") (class "Default")
      (node (ref "D3") (pin "A") (pinfunction "A_A") (pintype "passive"))
      (node (ref "L2") (pin "1") (pinfunction "1_1") (pintype "passive"))
      (node (ref "MT3608") (pin "1") (pinfunction "SW_1") (pintype "passive"))
    )
    (net (code "53") (name "Net-(OLED-Pad5)") (class "Default")
      (node (ref "OLED") (pin "5") (pinfunction "5_5") (pintype "passive"))
      (node (ref "R3") (pin "2") (pinfunction "2_2") (pintype "passive"))
    )
    (net (code "54") (name "Net-(OLED-Pad6)") (class "Default")
      (node (ref "OLED") (pin "6") (pinfunction "6_6") (pintype "passive"))
      (node (ref "R2") (pin "2") (pinfunction "2_2") (pintype "passive"))
    )
    (net (code "55") (name "Net-(OLED-Pad7)") (class "Default")
      (node (ref "OLED") (pin "7") (pinfunction "7_7") (pintype "passive"))
      (node (ref "R2") (pin "1") (pinfunction "1_1") (pintype "passive"))
    )
    (net (code "56") (name "Net-(SYS-K)") (class "Default")
      (node (ref "R7") (pin "2") (pinfunction "2_2") (pintype "passive"))
      (node (ref "SYS") (pin "2") (pinfunction "K_2") (pintype "passive"))
    )
    (net (code "57") (name "Net-(U2-BIAS)") (class "Default")
      (node (ref "C10") (pin "1") (pinfunction "1_1") (pintype "passive"))
      (node (ref "U2") (pin "12") (pinfunction "BIAS_12") (pintype "passive"))
    )
    (net (code "58") (name "Net-(U2-CG)") (class "Default")
      (node (ref "C8") (pin "2") (pinfunction "2_2") (pintype "passive"))
      (node (ref "U2") (pin "3") (pinfunction "CG_3") (pintype "passive"))
    )
    (net (code "59") (name "Net-(U2-CT)") (class "Default")
      (node (ref "C6") (pin "2") (pinfunction "2_2") (pintype "passive"))
      (node (ref "U2") (pin "1") (pinfunction "CT_1") (pintype "passive"))
    )
    (net (code "60") (name "Net-(U2-MICBIAS)") (class "Default")
      (node (ref "R1") (pin "2") (pinfunction "2_2") (pintype "passive"))
      (node (ref "R6") (pin "1") (pinfunction "1_1") (pintype "passive"))
      (node (ref "U2") (pin "13") (pinfunction "MICBIAS_13") (pintype "passive"))
    )
    (net (code "61") (name "Net-(U2-MICIN)") (class "Default")
      (node (ref "C9") (pin "1") (pinfunction "1_1") (pintype "passive"))
      (node (ref "U2") (pin "8") (pinfunction "MICIN_8") (pintype "passive"))
    )
    (net (code "62") (name "Net-(U2-TH)") (class "Default")
      (node (ref "R6") (pin "2") (pinfunction "2_2") (pintype "passive"))
      (node (ref "R8") (pin "2") (pinfunction "2_2") (pintype "passive"))
      (node (ref "U2") (pin "14") (pinfunction "TH_14") (pintype "passive"))
    )
    (net (code "63") (name "Net-(U3-FB)") (class "Default")
      (node (ref "R12") (pin "1") (pinfunction "1_1") (pintype "passive"))
      (node (ref "R9") (pin "2") (pinfunction "2_2") (pintype "passive"))
      (node (ref "U3") (pin "3") (pinfunction "FB_3") (pintype "passive"))
    )
    (net (code "64") (name "Net-(U3-VINA)") (class "Default")
      (node (ref "C28") (pin "2") (pinfunction "2_2") (pintype "passive"))
      (node (ref "U3") (pin "1") (pinfunction "VINA_1") (pintype "passive"))
    )
    (net (code "65") (name "Net-(U4-PROG)") (class "Default")
      (node (ref "R13") (pin "1") (pinfunction "1_1") (pintype "passive"))
      (node (ref "U4") (pin "6") (pinfunction "PROG_6") (pintype "passive"))
    )
    (net (code "66") (name "OLEDVPP") (class "Default")
      (node (ref "C11") (pin "1") (pinfunction "1_1") (pintype "passive"))
      (node (ref "C12") (pin "1") (pinfunction "1_1") (pintype "passive"))
      (node (ref "C7") (pin "1") (pinfunction "1_1") (pintype "passive"))
      (node (ref "D3") (pin "C") (pinfunction "C_C") (pintype "passive"))
      (node (ref "OLED") (pin "3") (pinfunction "3_3") (pintype "passive"))
      (node (ref "OLED") (pin "33") (pinfunction "33_33") (pintype "passive"))
      (node (ref "RB") (pin "1") (pinfunction "1_1") (pintype "passive"))
    )
    (net (code "67") (name "Power_PS") (class "Default")
      (node (ref "U1") (pin "46") (pinfunction "PB9_46") (pintype "passive"))
      (node (ref "U3") (pin "13") (pinfunction "PS/SY_13") (pintype "passive"))
    )
    (net (code "68") (name "unconnected-(CH340E-CTS#-Pad5)") (class "Default")
      (node (ref "CH340E") (pin "5") (pinfunction "CTS#_5") (pintype "passive"))
    )
    (net (code "69") (name "unconnected-(CH340E-RTS#-Pad4)") (class "Default")
      (node (ref "CH340E") (pin "4") (pinfunction "RTS#_4") (pintype "passive"))
    )
    (net (code "70") (name "unconnected-(CH340E-TNOW-Pad6)") (class "Default")
      (node (ref "CH340E") (pin "6") (pinfunction "TNOW_6") (pintype "passive"))
    )
    (net (code "71") (name "unconnected-(DS3231M-32kHZ-Pad1)") (class "Default")
      (node (ref "DS3231M") (pin "1") (pinfunction "32kHZ_1") (pintype "passive"))
    )
    (net (code "72") (name "unconnected-(DS3231M-RST-Pad4)") (class "Default")
      (node (ref "DS3231M") (pin "4") (pinfunction "RST_4") (pintype "passive"))
    )
    (net (code "73") (name "unconnected-(MT3608-NC-Pad6)") (class "Default")
      (node (ref "MT3608") (pin "6") (pinfunction "NC_6") (pintype "passive"))
    )
    (net (code "74") (name "unconnected-(OLED-Pad1)") (class "Default")
      (node (ref "OLED") (pin "1") (pinfunction "1_1") (pintype "passive+no_connect"))
    )
    (net (code "75") (name "unconnected-(OLED-Pad9)") (class "Default")
      (node (ref "OLED") (pin "9") (pinfunction "9_9") (pintype "passive+no_connect"))
    )
    (net (code "76") (name "unconnected-(OLED-Pad10)") (class "Default")
      (node (ref "OLED") (pin "10") (pinfunction "10_10") (pintype "passive"))
    )
    (net (code "77") (name "unconnected-(OLED-Pad11)") (class "Default")
      (node (ref "OLED") (pin "11") (pinfunction "11_11") (pintype "passive"))
    )
    (net (code "78") (name "unconnected-(OLED-Pad12)") (class "Default")
      (node (ref "OLED") (pin "12") (pinfunction "12_12") (pintype "passive"))
    )
    (net (code "79") (name "unconnected-(OLED-Pad13)") (class "Default")
      (node (ref "OLED") (pin "13") (pinfunction "13_13") (pintype "passive"))
    )
    (net (code "80") (name "unconnected-(OLED-Pad35)") (class "Default")
      (node (ref "OLED") (pin "35") (pinfunction "35_35") (pintype "passive+no_connect"))
    )
    (net (code "81") (name "unconnected-(U3-PG-Pad14)") (class "Default")
      (node (ref "U3") (pin "14") (pinfunction "PG_14") (pintype "passive"))
    )
    (net (code "82") (name "unconnected-(U4-STDBY-Pad5)") (class "Default")
      (node (ref "U4") (pin "5") (pinfunction "STDBY_5") (pintype "passive"))
    )
    (net (code "83") (name "unconnected-(USB-CC1-PadA5)") (class "Default")
      (node (ref "USB") (pin "A5") (pinfunction "CC1_A5") (pintype "passive"))
    )
    (net (code "84") (name "unconnected-(USB-CC2-PadB5)") (class "Default")
      (node (ref "USB") (pin "B5") (pinfunction "CC2_B5") (pintype "passive+no_connect"))
    )
    (net (code "85") (name "unconnected-(USB-RX1+-PadB11)") (class "Default")
      (node (ref "USB") (pin "B11") (pinfunction "RX1+_B11") (pintype "passive+no_connect"))
    )
    (net (code "86") (name "unconnected-(USB-RX1--PadB10)") (class "Default")
      (node (ref "USB") (pin "B10") (pinfunction "RX1-_B10") (pintype "passive+no_connect"))
    )
    (net (code "87") (name "unconnected-(USB-RX2+-PadA11)") (class "Default")
      (node (ref "USB") (pin "A11") (pinfunction "RX2+_A11") (pintype "passive+no_connect"))
    )
    (net (code "88") (name "unconnected-(USB-RX2--PadA10)") (class "Default")
      (node (ref "USB") (pin "A10") (pinfunction "RX2-_A10") (pintype "passive+no_connect"))
    )
    (net (code "89") (name "unconnected-(USB-SBU1-PadA8)") (class "Default")
      (node (ref "USB") (pin "A8") (pinfunction "SBU1_A8") (pintype "passive+no_connect"))
    )
    (net (code "90") (name "unconnected-(USB-SBU2-PadB8)") (class "Default")
      (node (ref "USB") (pin "B8") (pinfunction "SBU2_B8") (pintype "passive"))
    )
    (net (code "91") (name "unconnected-(USB-TX1+-PadA2)") (class "Default")
      (node (ref "USB") (pin "A2") (pinfunction "TX1+_A2") (pintype "passive+no_connect"))
    )
    (net (code "92") (name "unconnected-(USB-TX1--PadA3)") (class "Default")
      (node (ref "USB") (pin "A3") (pinfunction "TX1-_A3") (pintype "passive+no_connect"))
    )
    (net (code "93") (name "unconnected-(USB-TX2+-PadB2)") (class "Default")
      (node (ref "USB") (pin "B2") (pinfunction "TX2+_B2") (pintype "passive+no_connect"))
    )
    (net (code "94") (name "unconnected-(USB-TX2--PadB3)") (class "Default")
      (node (ref "USB") (pin "B3") (pinfunction "TX2-_B3") (pintype "passive+no_connect"))
    )
  )
)
